# PLACA_MAGO.net
KiCad netlist of a schematic drawn in EAGLE
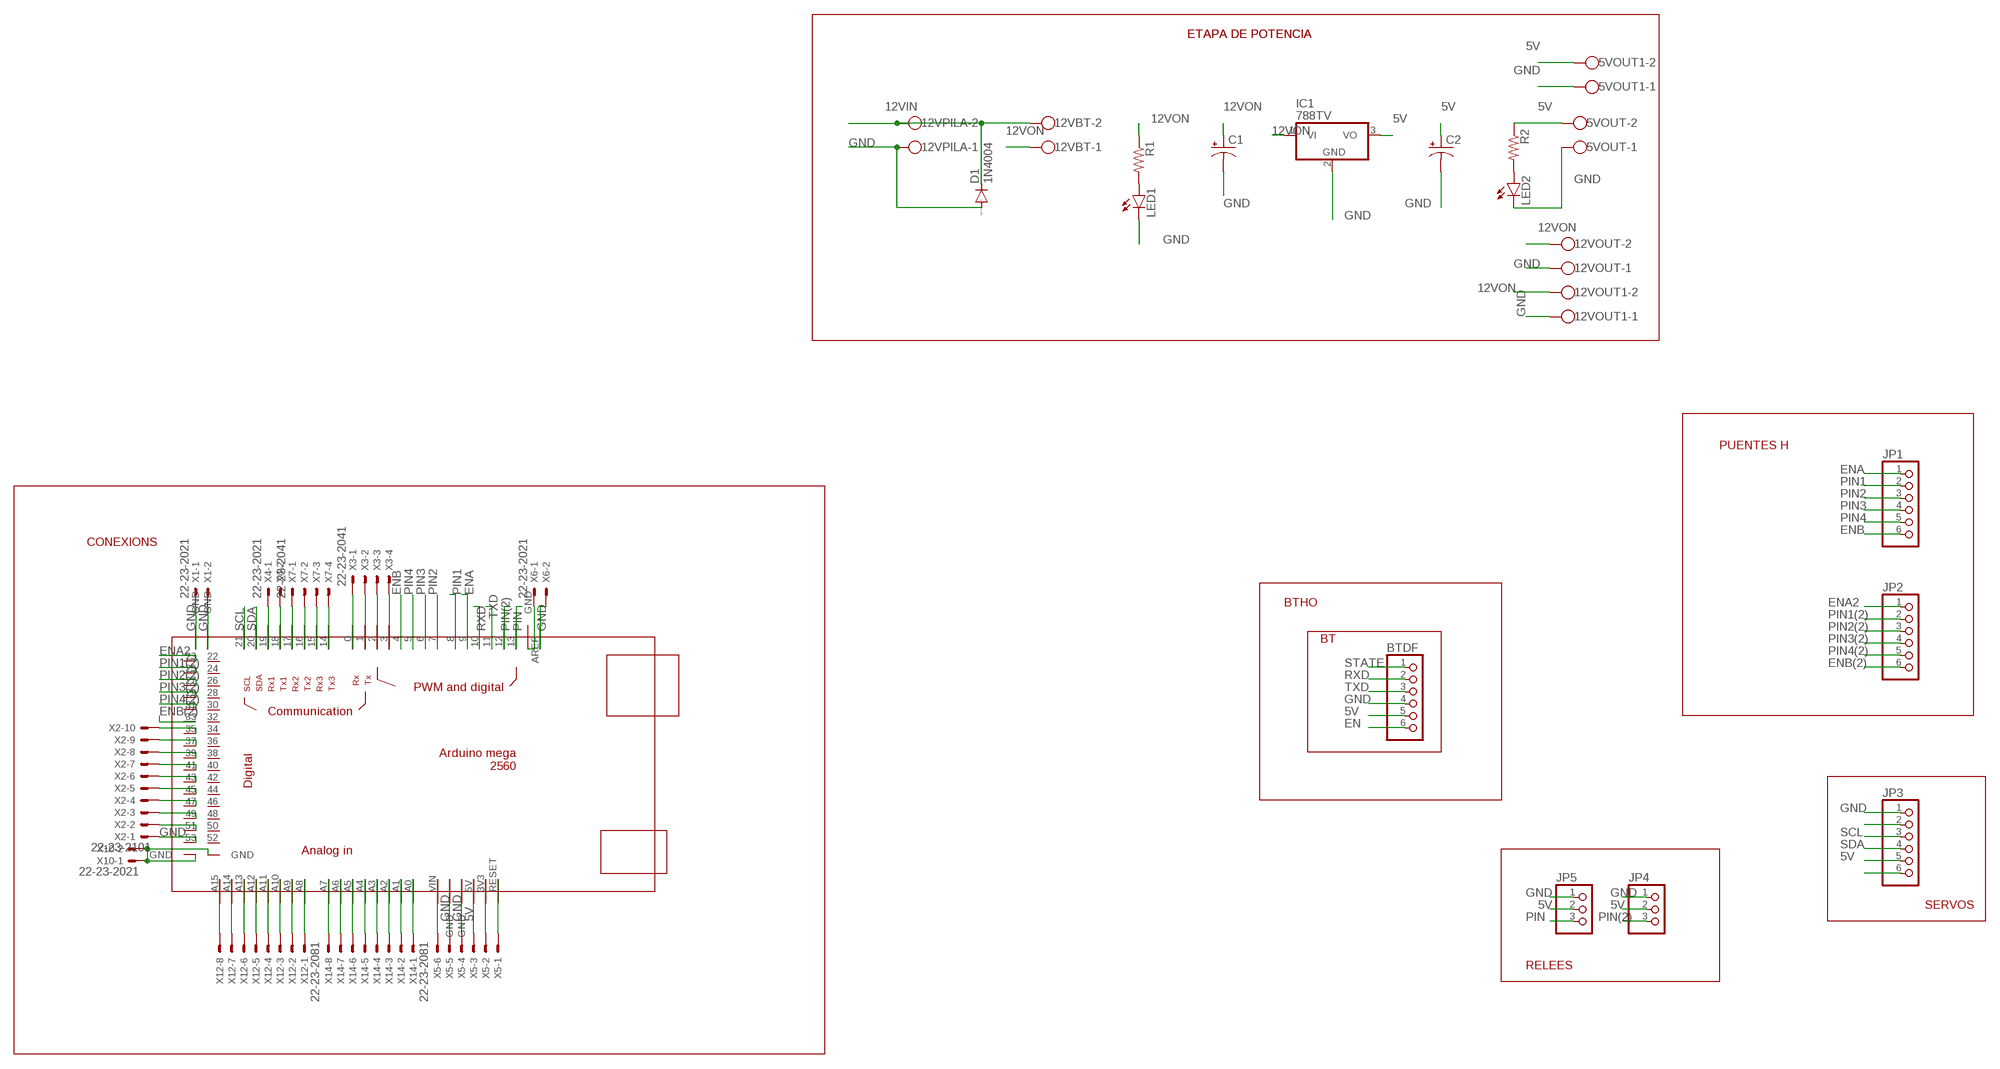
[diagram p0: schematic, sheet 1]

(export (version "E")
  (design (tool "Eeschema 10.0.6"))
  (components
    (comp (ref "5VOUT")
      (value "W237-102")
      (footprint "eagle-import:W237-102")
      (fields (field (name "MPN") "237-102"))
      (libsource (lib "eagle-import") (part "W237-102"))
    )
    (comp (ref "5VOUT1")
      (value "W237-102")
      (footprint "eagle-import:W237-102")
      (fields (field (name "MPN") "237-102"))
      (libsource (lib "eagle-import") (part "W237-102"))
    )
    (comp (ref "12VBT")
      (value "W237-102")
      (footprint "eagle-import:W237-102")
      (fields (field (name "MPN") "237-102"))
      (libsource (lib "eagle-import") (part "W237-102"))
    )
    (comp (ref "12VOUT")
      (value "W237-102")
      (footprint "eagle-import:W237-102")
      (fields (field (name "MPN") "237-102"))
      (libsource (lib "eagle-import") (part "W237-102"))
    )
    (comp (ref "12VOUT1")
      (value "W237-102")
      (footprint "eagle-import:W237-102")
      (fields (field (name "MPN") "237-102"))
      (libsource (lib "eagle-import") (part "W237-102"))
    )
    (comp (ref "12VPILA")
      (value "W237-102")
      (footprint "eagle-import:W237-102")
      (fields (field (name "MPN") "237-102"))
      (libsource (lib "eagle-import") (part "W237-102"))
    )
    (comp (ref "BTDF")
      (value "PINHD-1X6")
      (footprint "eagle-import:1X06")
      (libsource (lib "eagle-import") (part "PINHD-1X6"))
    )
    (comp (ref "C1")
      (value "CPOL-USE1.8-4")
      (footprint "eagle-import:E1,8-4")
      (libsource (lib "eagle-import") (part "CPOL-USE1.8-4"))
    )
    (comp (ref "C2")
      (value "CPOL-USE1.8-4")
      (footprint "eagle-import:E1,8-4")
      (libsource (lib "eagle-import") (part "CPOL-USE1.8-4"))
    )
    (comp (ref "D1")
      (value "1N4004")
      (footprint "eagle-import:DO41-10")
      (libsource (lib "eagle-import") (part "1N4004"))
    )
    (comp (ref "IC1")
      (value "788TV")
      (footprint "eagle-import:TO220V")
      (libsource (lib "eagle-import") (part "78TV8"))
    )
    (comp (ref "JP1")
      (value "PINHD-1X6")
      (footprint "eagle-import:1X06")
      (libsource (lib "eagle-import") (part "pinhead_325_PINHD-1X6"))
    )
    (comp (ref "JP2")
      (value "PINHD-1X6")
      (footprint "eagle-import:1X06")
      (libsource (lib "eagle-import") (part "pinhead_325_PINHD-1X6"))
    )
    (comp (ref "JP3")
      (value "PINHD-1X6")
      (footprint "eagle-import:1X06")
      (libsource (lib "eagle-import") (part "pinhead_325_PINHD-1X6"))
    )
    (comp (ref "JP4")
      (value "PINHD-1X3")
      (footprint "eagle-import:1X03")
      (libsource (lib "eagle-import") (part "PINHD-1X3"))
    )
    (comp (ref "JP5")
      (value "PINHD-1X3")
      (footprint "eagle-import:1X03")
      (libsource (lib "eagle-import") (part "PINHD-1X3"))
    )
    (comp (ref "LED1")
      (value "LED5MM")
      (footprint "eagle-import:LED5MM")
      (libsource (lib "eagle-import") (part "LED5MM"))
    )
    (comp (ref "LED2")
      (value "LED5MM")
      (footprint "eagle-import:LED5MM")
      (libsource (lib "eagle-import") (part "LED5MM"))
    )
    (comp (ref "R1")
      (value "R-US_0204/7")
      (footprint "eagle-import:0204_7")
      (libsource (lib "eagle-import") (part "R-US_0204/7"))
    )
    (comp (ref "R2")
      (value "R-US_0204/7")
      (footprint "eagle-import:0204_7")
      (libsource (lib "eagle-import") (part "R-US_0204/7"))
    )
    (comp (ref "U$1")
      (value "MEGA_DEVICE")
      (footprint "eagle-import:MEGAOUTLINE")
      (libsource (lib "eagle-import") (part "MEGA_DEVICE"))
    )
    (comp (ref "X1")
      (value "22-23-2021")
      (footprint "eagle-import:22-23-2021")
      (fields (field (name "MF") "MOLEX"))
      (libsource (lib "eagle-import") (part "22-23-2021"))
    )
    (comp (ref "X2")
      (value "22-23-2101")
      (footprint "eagle-import:22-23-2101")
      (fields (field (name "MF") "MOLEX"))
      (libsource (lib "eagle-import") (part "22-23-2101"))
    )
    (comp (ref "X3")
      (value "22-23-2041")
      (footprint "eagle-import:22-23-2041")
      (fields (field (name "MF") "MOLEX"))
      (libsource (lib "eagle-import") (part "22-23-2041"))
    )
    (comp (ref "X4")
      (value "22-23-2021")
      (footprint "eagle-import:22-23-2021")
      (fields (field (name "MF") "MOLEX"))
      (libsource (lib "eagle-import") (part "22-23-2021"))
    )
    (comp (ref "X5")
      (value "22-23-2061")
      (footprint "eagle-import:22-23-2061")
      (fields (field (name "MF") "MOLEX"))
      (libsource (lib "eagle-import") (part "22-23-2061"))
    )
    (comp (ref "X6")
      (value "22-23-2021")
      (footprint "eagle-import:22-23-2021")
      (fields (field (name "MF") "MOLEX"))
      (libsource (lib "eagle-import") (part "22-23-2021"))
    )
    (comp (ref "X7")
      (value "22-23-2041")
      (footprint "eagle-import:22-23-2041")
      (fields (field (name "MF") "MOLEX"))
      (libsource (lib "eagle-import") (part "22-23-2041"))
    )
    (comp (ref "X10")
      (value "22-23-2021")
      (footprint "eagle-import:22-23-2021")
      (fields (field (name "MF") "MOLEX"))
      (libsource (lib "eagle-import") (part "22-23-2021"))
    )
    (comp (ref "X12")
      (value "22-23-2081")
      (footprint "eagle-import:22-23-2081")
      (fields (field (name "MF") "MOLEX"))
      (libsource (lib "eagle-import") (part "22-23-2081"))
    )
    (comp (ref "X14")
      (value "22-23-2081")
      (footprint "eagle-import:22-23-2081")
      (fields (field (name "MF") "MOLEX"))
      (libsource (lib "eagle-import") (part "22-23-2081"))
    )
  )
  (nets
    (net (code "1") (name "/5V") (class "Default")
      (node (ref "5VOUT") (pin "2") (pinfunction "KL_2") (pintype "passive"))
      (node (ref "5VOUT1") (pin "2") (pinfunction "KL_2") (pintype "passive"))
      (node (ref "BTDF") (pin "5") (pinfunction "5_5") (pintype "passive"))
      (node (ref "C2") (pin "+") (pinfunction "+_+") (pintype "passive"))
      (node (ref "IC1") (pin "3") (pinfunction "VO_3") (pintype "passive"))
      (node (ref "JP3") (pin "5") (pinfunction "5_5") (pintype "passive"))
      (node (ref "JP4") (pin "2") (pinfunction "2_2") (pintype "passive"))
      (node (ref "JP5") (pin "2") (pinfunction "2_2") (pintype "passive"))
      (node (ref "R2") (pin "1") (pinfunction "1_1") (pintype "passive"))
      (node (ref "U$1") (pin "5V") (pinfunction "5V_5V") (pintype "bidirectional"))
      (node (ref "X5") (pin "3") (pinfunction "S_3") (pintype "passive"))
    )
    (net (code "2") (name "/12VIN") (class "Default")
      (node (ref "12VBT") (pin "2") (pinfunction "KL_2") (pintype "passive"))
      (node (ref "12VPILA") (pin "2") (pinfunction "KL_2") (pintype "passive"))
      (node (ref "D1") (pin "C") (pinfunction "C_C") (pintype "passive"))
    )
    (net (code "3") (name "/12VON") (class "Default")
      (node (ref "12VBT") (pin "1") (pinfunction "KL_1") (pintype "passive"))
      (node (ref "12VOUT") (pin "2") (pinfunction "KL_2") (pintype "passive"))
      (node (ref "12VOUT1") (pin "2") (pinfunction "KL_2") (pintype "passive"))
      (node (ref "C1") (pin "+") (pinfunction "+_+") (pintype "passive"))
      (node (ref "IC1") (pin "1") (pinfunction "VI_1") (pintype "input"))
      (node (ref "R1") (pin "1") (pinfunction "1_1") (pintype "passive"))
    )
    (net (code "4") (name "/EN") (class "Default")
      (node (ref "BTDF") (pin "6") (pinfunction "6_6") (pintype "passive"))
    )
    (net (code "5") (name "/ENA") (class "Default")
      (node (ref "JP1") (pin "1") (pinfunction "1_1") (pintype "passive"))
      (node (ref "U$1") (pin "9") (pinfunction "9_9") (pintype "bidirectional"))
    )
    (net (code "6") (name "/ENA2") (class "Default")
      (node (ref "JP2") (pin "1") (pinfunction "1_1") (pintype "passive"))
      (node (ref "U$1") (pin "23") (pinfunction "23_23") (pintype "bidirectional"))
    )
    (net (code "7") (name "/ENB") (class "Default")
      (node (ref "JP1") (pin "6") (pinfunction "6_6") (pintype "passive"))
      (node (ref "U$1") (pin "4") (pinfunction "4_4") (pintype "bidirectional"))
    )
    (net (code "8") (name "/ENB(2)") (class "Default")
      (node (ref "JP2") (pin "6") (pinfunction "6_6") (pintype "passive"))
      (node (ref "U$1") (pin "33") (pinfunction "33_33") (pintype "bidirectional"))
    )
    (net (code "9") (name "/GND") (class "Default")
      (node (ref "12VOUT") (pin "1") (pinfunction "KL_1") (pintype "passive"))
      (node (ref "12VOUT1") (pin "1") (pinfunction "KL_1") (pintype "passive"))
      (node (ref "12VPILA") (pin "1") (pinfunction "KL_1") (pintype "passive"))
      (node (ref "5VOUT") (pin "1") (pinfunction "KL_1") (pintype "passive"))
      (node (ref "5VOUT1") (pin "1") (pinfunction "KL_1") (pintype "passive"))
      (node (ref "BTDF") (pin "4") (pinfunction "4_4") (pintype "passive"))
      (node (ref "C1") (pin "-") (pinfunction "-_-") (pintype "passive"))
      (node (ref "C2") (pin "-") (pinfunction "-_-") (pintype "passive"))
      (node (ref "D1") (pin "A") (pinfunction "A_A") (pintype "passive"))
      (node (ref "IC1") (pin "2") (pinfunction "GND_2") (pintype "passive"))
      (node (ref "JP3") (pin "1") (pinfunction "1_1") (pintype "passive"))
      (node (ref "JP4") (pin "1") (pinfunction "1_1") (pintype "passive"))
      (node (ref "JP5") (pin "1") (pinfunction "1_1") (pintype "passive"))
      (node (ref "LED1") (pin "K") (pinfunction "C_K") (pintype "passive"))
      (node (ref "LED2") (pin "K") (pinfunction "C_K") (pintype "passive"))
      (node (ref "U$1") (pin "GND@1") (pinfunction "GND_GND@1") (pintype "bidirectional"))
      (node (ref "U$1") (pin "GND@2") (pinfunction "GND_GND@2") (pintype "bidirectional"))
      (node (ref "U$1") (pin "GND@3") (pinfunction "GND_GND@3") (pintype "bidirectional"))
      (node (ref "U$1") (pin "GND@4") (pinfunction "GND_GND@4") (pintype "bidirectional"))
      (node (ref "U$1") (pin "GND@5") (pinfunction "GND_GND@5") (pintype "bidirectional"))
      (node (ref "U$1") (pin "GND@6") (pinfunction "GND_GND@6") (pintype "bidirectional"))
      (node (ref "U$1") (pin "GND@7") (pinfunction "GND_GND@7") (pintype "bidirectional"))
      (node (ref "X1") (pin "1") (pinfunction "S_1") (pintype "passive"))
      (node (ref "X1") (pin "2") (pinfunction "S_2") (pintype "passive"))
      (node (ref "X10") (pin "1") (pinfunction "S_1") (pintype "passive"))
      (node (ref "X10") (pin "2") (pinfunction "S_2") (pintype "passive"))
      (node (ref "X5") (pin "4") (pinfunction "S_4") (pintype "passive"))
      (node (ref "X5") (pin "5") (pinfunction "S_5") (pintype "passive"))
      (node (ref "X6") (pin "1") (pinfunction "S_1") (pintype "passive"))
    )
    (net (code "10") (name "/PIN") (class "Default")
      (node (ref "JP5") (pin "3") (pinfunction "3_3") (pintype "passive"))
      (node (ref "U$1") (pin "13") (pinfunction "13_13") (pintype "bidirectional"))
    )
    (net (code "11") (name "/PIN(2)") (class "Default")
      (node (ref "JP4") (pin "3") (pinfunction "3_3") (pintype "passive"))
      (node (ref "U$1") (pin "12") (pinfunction "12_12") (pintype "bidirectional"))
    )
    (net (code "12") (name "/PIN1") (class "Default")
      (node (ref "JP1") (pin "2") (pinfunction "2_2") (pintype "passive"))
      (node (ref "U$1") (pin "8") (pinfunction "8_8") (pintype "bidirectional"))
    )
    (net (code "13") (name "/PIN1(2)") (class "Default")
      (node (ref "JP2") (pin "2") (pinfunction "2_2") (pintype "passive"))
      (node (ref "U$1") (pin "25") (pinfunction "25_25") (pintype "bidirectional"))
    )
    (net (code "14") (name "/PIN2") (class "Default")
      (node (ref "JP1") (pin "3") (pinfunction "3_3") (pintype "passive"))
      (node (ref "U$1") (pin "7") (pinfunction "7_7") (pintype "bidirectional"))
    )
    (net (code "15") (name "/PIN2(2)") (class "Default")
      (node (ref "JP2") (pin "3") (pinfunction "3_3") (pintype "passive"))
      (node (ref "U$1") (pin "27") (pinfunction "27_27") (pintype "bidirectional"))
    )
    (net (code "16") (name "/PIN3") (class "Default")
      (node (ref "JP1") (pin "4") (pinfunction "4_4") (pintype "passive"))
      (node (ref "U$1") (pin "6") (pinfunction "6_6") (pintype "bidirectional"))
    )
    (net (code "17") (name "/PIN3(2)") (class "Default")
      (node (ref "JP2") (pin "4") (pinfunction "4_4") (pintype "passive"))
      (node (ref "U$1") (pin "29") (pinfunction "29_29") (pintype "bidirectional"))
    )
    (net (code "18") (name "/PIN4") (class "Default")
      (node (ref "JP1") (pin "5") (pinfunction "5_5") (pintype "passive"))
      (node (ref "U$1") (pin "5") (pinfunction "5_5") (pintype "bidirectional"))
    )
    (net (code "19") (name "/PIN4(2)") (class "Default")
      (node (ref "JP2") (pin "5") (pinfunction "5_5") (pintype "passive"))
      (node (ref "U$1") (pin "31") (pinfunction "31_31") (pintype "bidirectional"))
    )
    (net (code "20") (name "/RXD") (class "Default")
      (node (ref "BTDF") (pin "2") (pinfunction "2_2") (pintype "passive"))
      (node (ref "U$1") (pin "10") (pinfunction "10_10") (pintype "bidirectional"))
    )
    (net (code "21") (name "/SCL") (class "Default")
      (node (ref "JP3") (pin "3") (pinfunction "3_3") (pintype "passive"))
      (node (ref "U$1") (pin "21") (pinfunction "21_21") (pintype "bidirectional"))
    )
    (net (code "22") (name "/SDA") (class "Default")
      (node (ref "JP3") (pin "4") (pinfunction "4_4") (pintype "passive"))
      (node (ref "U$1") (pin "20") (pinfunction "20_20") (pintype "bidirectional"))
    )
    (net (code "23") (name "/STATE") (class "Default")
      (node (ref "BTDF") (pin "1") (pinfunction "1_1") (pintype "passive"))
    )
    (net (code "24") (name "/TXD") (class "Default")
      (node (ref "BTDF") (pin "3") (pinfunction "3_3") (pintype "passive"))
      (node (ref "U$1") (pin "11") (pinfunction "11_11") (pintype "bidirectional"))
    )
    (net (code "25") (name "Net-(LED1-PadA)") (class "Default")
      (node (ref "LED1") (pin "A") (pinfunction "A_A") (pintype "passive"))
      (node (ref "R1") (pin "2") (pinfunction "2_2") (pintype "passive"))
    )
    (net (code "26") (name "Net-(LED2-PadA)") (class "Default")
      (node (ref "LED2") (pin "A") (pinfunction "A_A") (pintype "passive"))
      (node (ref "R2") (pin "2") (pinfunction "2_2") (pintype "passive"))
    )
    (net (code "27") (name "Net-(X2A-S)") (class "Default")
      (node (ref "U$1") (pin "53") (pinfunction "53_53") (pintype "bidirectional"))
      (node (ref "X2") (pin "1") (pinfunction "S_1") (pintype "passive"))
    )
    (net (code "28") (name "Net-(X2B-S)") (class "Default")
      (node (ref "U$1") (pin "35") (pinfunction "35_35") (pintype "bidirectional"))
      (node (ref "X2") (pin "10") (pinfunction "S_10") (pintype "passive"))
    )
    (net (code "29") (name "Net-(X2C-S)") (class "Default")
      (node (ref "U$1") (pin "51") (pinfunction "51_51") (pintype "bidirectional"))
      (node (ref "X2") (pin "2") (pinfunction "S_2") (pintype "passive"))
    )
    (net (code "30") (name "Net-(X2D-S)") (class "Default")
      (node (ref "U$1") (pin "49") (pinfunction "49_49") (pintype "bidirectional"))
      (node (ref "X2") (pin "3") (pinfunction "S_3") (pintype "passive"))
    )
    (net (code "31") (name "Net-(X2E-S)") (class "Default")
      (node (ref "U$1") (pin "47") (pinfunction "47_47") (pintype "bidirectional"))
      (node (ref "X2") (pin "4") (pinfunction "S_4") (pintype "passive"))
    )
    (net (code "32") (name "Net-(X2F-S)") (class "Default")
      (node (ref "U$1") (pin "45") (pinfunction "45_45") (pintype "bidirectional"))
      (node (ref "X2") (pin "5") (pinfunction "S_5") (pintype "passive"))
    )
    (net (code "33") (name "Net-(X2G-S)") (class "Default")
      (node (ref "U$1") (pin "43") (pinfunction "43_43") (pintype "bidirectional"))
      (node (ref "X2") (pin "6") (pinfunction "S_6") (pintype "passive"))
    )
    (net (code "34") (name "Net-(X2H-S)") (class "Default")
      (node (ref "U$1") (pin "41") (pinfunction "41_41") (pintype "bidirectional"))
      (node (ref "X2") (pin "7") (pinfunction "S_7") (pintype "passive"))
    )
    (net (code "35") (name "Net-(X2I-S)") (class "Default")
      (node (ref "U$1") (pin "39") (pinfunction "39_39") (pintype "bidirectional"))
      (node (ref "X2") (pin "8") (pinfunction "S_8") (pintype "passive"))
    )
    (net (code "36") (name "Net-(X2J-S)") (class "Default")
      (node (ref "U$1") (pin "37") (pinfunction "37_37") (pintype "bidirectional"))
      (node (ref "X2") (pin "9") (pinfunction "S_9") (pintype "passive"))
    )
    (net (code "37") (name "Net-(X3A-S)") (class "Default")
      (node (ref "U$1") (pin "0") (pinfunction "0_0") (pintype "bidirectional"))
      (node (ref "X3") (pin "1") (pinfunction "S_1") (pintype "passive"))
    )
    (net (code "38") (name "Net-(X3B-S)") (class "Default")
      (node (ref "U$1") (pin "1") (pinfunction "1_1") (pintype "bidirectional"))
      (node (ref "X3") (pin "2") (pinfunction "S_2") (pintype "passive"))
    )
    (net (code "39") (name "Net-(X3C-S)") (class "Default")
      (node (ref "U$1") (pin "2") (pinfunction "2_2") (pintype "bidirectional"))
      (node (ref "X3") (pin "3") (pinfunction "S_3") (pintype "passive"))
    )
    (net (code "40") (name "Net-(X3D-S)") (class "Default")
      (node (ref "U$1") (pin "3") (pinfunction "3_3") (pintype "bidirectional"))
      (node (ref "X3") (pin "4") (pinfunction "S_4") (pintype "passive"))
    )
    (net (code "41") (name "Net-(X4A-S)") (class "Default")
      (node (ref "U$1") (pin "19") (pinfunction "19_19") (pintype "bidirectional"))
      (node (ref "X4") (pin "1") (pinfunction "S_1") (pintype "passive"))
    )
    (net (code "42") (name "Net-(X4B-S)") (class "Default")
      (node (ref "U$1") (pin "18") (pinfunction "18_18") (pintype "bidirectional"))
      (node (ref "X4") (pin "2") (pinfunction "S_2") (pintype "passive"))
    )
    (net (code "43") (name "Net-(X5A-S)") (class "Default")
      (node (ref "U$1") (pin "RESET") (pinfunction "RESET_RESET") (pintype "bidirectional"))
      (node (ref "X5") (pin "1") (pinfunction "S_1") (pintype "passive"))
    )
    (net (code "44") (name "Net-(X5B-S)") (class "Default")
      (node (ref "U$1") (pin "3V3") (pinfunction "3V3_3V3") (pintype "bidirectional"))
      (node (ref "X5") (pin "2") (pinfunction "S_2") (pintype "passive"))
    )
    (net (code "45") (name "Net-(X5F-S)") (class "Default")
      (node (ref "U$1") (pin "VIN") (pinfunction "VIN_VIN") (pintype "bidirectional"))
      (node (ref "X5") (pin "6") (pinfunction "S_6") (pintype "passive"))
    )
    (net (code "46") (name "Net-(X6B-S)") (class "Default")
      (node (ref "U$1") (pin "AREF") (pinfunction "AREF_AREF") (pintype "bidirectional"))
      (node (ref "X6") (pin "2") (pinfunction "S_2") (pintype "passive"))
    )
    (net (code "47") (name "Net-(X7A-S)") (class "Default")
      (node (ref "U$1") (pin "17") (pinfunction "17_17") (pintype "bidirectional"))
      (node (ref "X7") (pin "1") (pinfunction "S_1") (pintype "passive"))
    )
    (net (code "48") (name "Net-(X7B-S)") (class "Default")
      (node (ref "U$1") (pin "16") (pinfunction "16_16") (pintype "bidirectional"))
      (node (ref "X7") (pin "2") (pinfunction "S_2") (pintype "passive"))
    )
    (net (code "49") (name "Net-(X7C-S)") (class "Default")
      (node (ref "U$1") (pin "15") (pinfunction "15_15") (pintype "bidirectional"))
      (node (ref "X7") (pin "3") (pinfunction "S_3") (pintype "passive"))
    )
    (net (code "50") (name "Net-(X7D-S)") (class "Default")
      (node (ref "U$1") (pin "14") (pinfunction "14_14") (pintype "bidirectional"))
      (node (ref "X7") (pin "4") (pinfunction "S_4") (pintype "passive"))
    )
    (net (code "51") (name "Net-(X12A-S)") (class "Default")
      (node (ref "U$1") (pin "A8") (pinfunction "A8_A8") (pintype "bidirectional"))
      (node (ref "X12") (pin "1") (pinfunction "S_1") (pintype "passive"))
    )
    (net (code "52") (name "Net-(X12B-S)") (class "Default")
      (node (ref "U$1") (pin "A9") (pinfunction "A9_A9") (pintype "bidirectional"))
      (node (ref "X12") (pin "2") (pinfunction "S_2") (pintype "passive"))
    )
    (net (code "53") (name "Net-(X12C-S)") (class "Default")
      (node (ref "U$1") (pin "A10") (pinfunction "A10_A10") (pintype "bidirectional"))
      (node (ref "X12") (pin "3") (pinfunction "S_3") (pintype "passive"))
    )
    (net (code "54") (name "Net-(X12D-S)") (class "Default")
      (node (ref "U$1") (pin "A11") (pinfunction "A11_A11") (pintype "bidirectional"))
      (node (ref "X12") (pin "4") (pinfunction "S_4") (pintype "passive"))
    )
    (net (code "55") (name "Net-(X12E-S)") (class "Default")
      (node (ref "U$1") (pin "A12") (pinfunction "A12_A12") (pintype "bidirectional"))
      (node (ref "X12") (pin "5") (pinfunction "S_5") (pintype "passive"))
    )
    (net (code "56") (name "Net-(X12F-S)") (class "Default")
      (node (ref "U$1") (pin "A13") (pinfunction "A13_A13") (pintype "bidirectional"))
      (node (ref "X12") (pin "6") (pinfunction "S_6") (pintype "passive"))
    )
    (net (code "57") (name "Net-(X12G-S)") (class "Default")
      (node (ref "U$1") (pin "A14") (pinfunction "A14_A14") (pintype "bidirectional"))
      (node (ref "X12") (pin "7") (pinfunction "S_7") (pintype "passive"))
    )
    (net (code "58") (name "Net-(X12H-S)") (class "Default")
      (node (ref "U$1") (pin "A15") (pinfunction "A15_A15") (pintype "bidirectional"))
      (node (ref "X12") (pin "8") (pinfunction "S_8") (pintype "passive"))
    )
    (net (code "59") (name "Net-(X14A-S)") (class "Default")
      (node (ref "U$1") (pin "A0") (pinfunction "A0_A0") (pintype "bidirectional"))
      (node (ref "X14") (pin "1") (pinfunction "S_1") (pintype "passive"))
    )
    (net (code "60") (name "Net-(X14B-S)") (class "Default")
      (node (ref "U$1") (pin "A1") (pinfunction "A1_A1") (pintype "bidirectional"))
      (node (ref "X14") (pin "2") (pinfunction "S_2") (pintype "passive"))
    )
    (net (code "61") (name "Net-(X14C-S)") (class "Default")
      (node (ref "U$1") (pin "A2") (pinfunction "A2_A2") (pintype "bidirectional"))
      (node (ref "X14") (pin "3") (pinfunction "S_3") (pintype "passive"))
    )
    (net (code "62") (name "Net-(X14D-S)") (class "Default")
      (node (ref "U$1") (pin "A3") (pinfunction "A3_A3") (pintype "bidirectional"))
      (node (ref "X14") (pin "4") (pinfunction "S_4") (pintype "passive"))
    )
    (net (code "63") (name "Net-(X14E-S)") (class "Default")
      (node (ref "U$1") (pin "A4") (pinfunction "A4_A4") (pintype "bidirectional"))
      (node (ref "X14") (pin "5") (pinfunction "S_5") (pintype "passive"))
    )
    (net (code "64") (name "Net-(X14F-S)") (class "Default")
      (node (ref "U$1") (pin "A5") (pinfunction "A5_A5") (pintype "bidirectional"))
      (node (ref "X14") (pin "6") (pinfunction "S_6") (pintype "passive"))
    )
    (net (code "65") (name "Net-(X14G-S)") (class "Default")
      (node (ref "U$1") (pin "A6") (pinfunction "A6_A6") (pintype "bidirectional"))
      (node (ref "X14") (pin "7") (pinfunction "S_7") (pintype "passive"))
    )
    (net (code "66") (name "Net-(X14H-S)") (class "Default")
      (node (ref "U$1") (pin "A7") (pinfunction "A7_A7") (pintype "bidirectional"))
      (node (ref "X14") (pin "8") (pinfunction "S_8") (pintype "passive"))
    )
    (net (code "67") (name "unconnected-(JP3-Pad2)") (class "Default")
      (node (ref "JP3") (pin "2") (pinfunction "2_2") (pintype "passive"))
    )
    (net (code "68") (name "unconnected-(JP3-Pad6)") (class "Default")
      (node (ref "JP3") (pin "6") (pinfunction "6_6") (pintype "passive"))
    )
    (net (code "69") (name "unconnected-(U$1-Pad22)") (class "Default")
      (node (ref "U$1") (pin "22") (pinfunction "22_22") (pintype "bidirectional"))
    )
    (net (code "70") (name "unconnected-(U$1-Pad24)") (class "Default")
      (node (ref "U$1") (pin "24") (pinfunction "24_24") (pintype "bidirectional"))
    )
    (net (code "71") (name "unconnected-(U$1-Pad26)") (class "Default")
      (node (ref "U$1") (pin "26") (pinfunction "26_26") (pintype "bidirectional"))
    )
    (net (code "72") (name "unconnected-(U$1-Pad28)") (class "Default")
      (node (ref "U$1") (pin "28") (pinfunction "28_28") (pintype "bidirectional"))
    )
    (net (code "73") (name "unconnected-(U$1-Pad30)") (class "Default")
      (node (ref "U$1") (pin "30") (pinfunction "30_30") (pintype "bidirectional"))
    )
    (net (code "74") (name "unconnected-(U$1-Pad32)") (class "Default")
      (node (ref "U$1") (pin "32") (pinfunction "32_32") (pintype "bidirectional"))
    )
    (net (code "75") (name "unconnected-(U$1-Pad34)") (class "Default")
      (node (ref "U$1") (pin "34") (pinfunction "34_34") (pintype "bidirectional"))
    )
    (net (code "76") (name "unconnected-(U$1-Pad36)") (class "Default")
      (node (ref "U$1") (pin "36") (pinfunction "36_36") (pintype "bidirectional"))
    )
    (net (code "77") (name "unconnected-(U$1-Pad38)") (class "Default")
      (node (ref "U$1") (pin "38") (pinfunction "38_38") (pintype "bidirectional"))
    )
    (net (code "78") (name "unconnected-(U$1-Pad40)") (class "Default")
      (node (ref "U$1") (pin "40") (pinfunction "40_40") (pintype "bidirectional"))
    )
    (net (code "79") (name "unconnected-(U$1-Pad42)") (class "Default")
      (node (ref "U$1") (pin "42") (pinfunction "42_42") (pintype "bidirectional"))
    )
    (net (code "80") (name "unconnected-(U$1-Pad44)") (class "Default")
      (node (ref "U$1") (pin "44") (pinfunction "44_44") (pintype "bidirectional"))
    )
    (net (code "81") (name "unconnected-(U$1-Pad46)") (class "Default")
      (node (ref "U$1") (pin "46") (pinfunction "46_46") (pintype "bidirectional"))
    )
    (net (code "82") (name "unconnected-(U$1-Pad48)") (class "Default")
      (node (ref "U$1") (pin "48") (pinfunction "48_48") (pintype "bidirectional"))
    )
    (net (code "83") (name "unconnected-(U$1-Pad50)") (class "Default")
      (node (ref "U$1") (pin "50") (pinfunction "50_50") (pintype "bidirectional"))
    )
    (net (code "84") (name "unconnected-(U$1-Pad52)") (class "Default")
      (node (ref "U$1") (pin "52") (pinfunction "52_52") (pintype "bidirectional"))
    )
  )
)
